# V1_0.net
KiCad netlist of a schematic drawn in Altium Designer
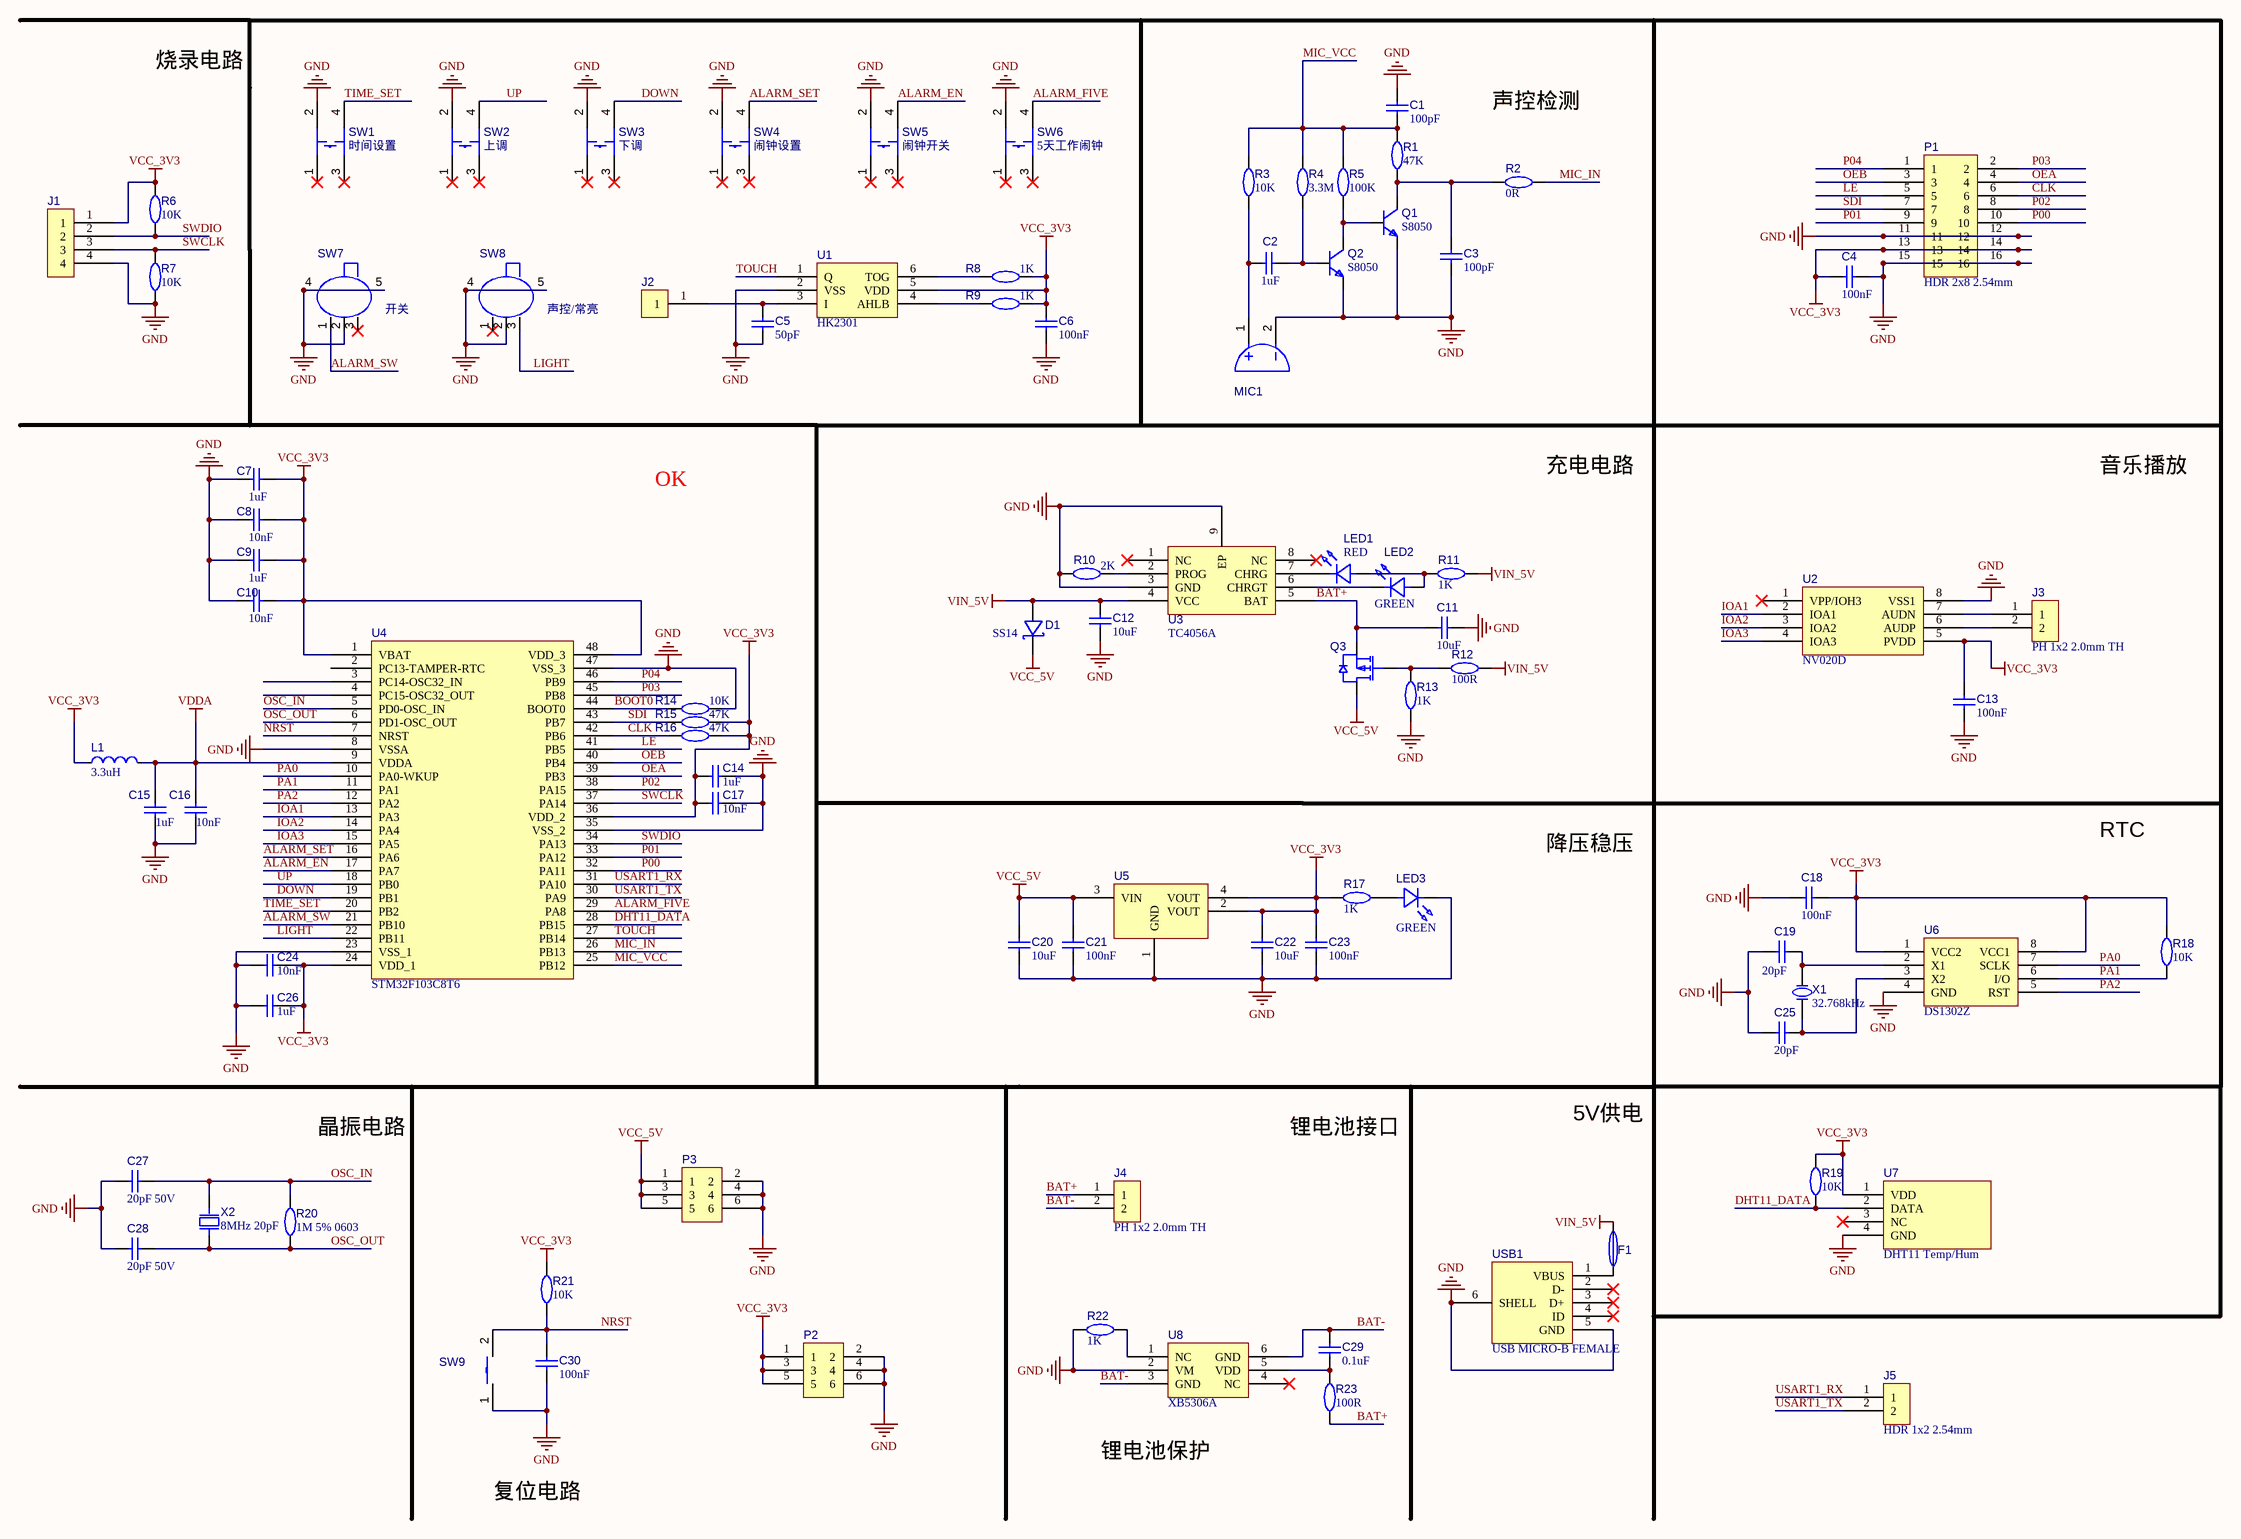
[diagram p0: 温湿度闹钟_V1.0.SchDoc]

(export (version "E")
  (design (tool "Eeschema 10.0.6"))
  (components
    (comp (ref "C1")
      (value "100pF")
      (footprint "C0603")
      (description "贴片电容")
      (libsource (lib "ADlib") (part "CAP_C0603_50V_10nF 50V"))
    )
    (comp (ref "C2")
      (value "1uF")
      (footprint "C0603")
      (description "贴片电容")
      (libsource (lib "ADlib") (part "CAP_C0603_50V_10nF 50V"))
    )
    (comp (ref "C3")
      (value "100pF")
      (footprint "C0603")
      (description "贴片电容")
      (libsource (lib "ADlib") (part "CAP_C0603_50V_10nF 50V"))
    )
    (comp (ref "C4")
      (value "100nF")
      (footprint "C0603")
      (description "贴片电容")
      (libsource (lib "ADlib") (part "CAP_C0603_50V_10nF 50V"))
    )
    (comp (ref "C5")
      (value "50pF")
      (footprint "C0603")
      (description "贴片电容")
      (libsource (lib "ADlib") (part "CAP_C0603_50V_10nF 50V"))
    )
    (comp (ref "C6")
      (value "100nF")
      (footprint "C0603")
      (description "贴片电容")
      (libsource (lib "ADlib") (part "CAP_C0603_50V_10nF 50V"))
    )
    (comp (ref "C7")
      (value "1uF")
      (footprint "C0603")
      (description "贴片电容")
      (libsource (lib "ADlib") (part "CAP_C0603_50V_10nF 50V"))
    )
    (comp (ref "C8")
      (value "10nF")
      (footprint "C0603")
      (description "贴片电容")
      (libsource (lib "ADlib") (part "CAP_C0603_50V_10nF 50V"))
    )
    (comp (ref "C9")
      (value "1uF")
      (footprint "C0603")
      (description "贴片电容")
      (libsource (lib "ADlib") (part "CAP_C0603_50V_10nF 50V"))
    )
    (comp (ref "C10")
      (value "10nF")
      (footprint "C0603")
      (description "贴片电容")
      (libsource (lib "ADlib") (part "CAP_C0603_50V_10nF 50V"))
    )
    (comp (ref "C11")
      (value "10uF")
      (footprint "C0603")
      (description "贴片电容")
      (libsource (lib "ADlib") (part "CAP_C0603_50V_10nF 50V"))
    )
    (comp (ref "C12")
      (value "10uF")
      (footprint "C0603")
      (description "贴片电容")
      (libsource (lib "ADlib") (part "CAP_C0603_50V_10nF 50V"))
    )
    (comp (ref "C13")
      (value "100nF")
      (footprint "C0603")
      (description "贴片电容")
      (libsource (lib "ADlib") (part "CAP_C0603_50V_10nF 50V"))
    )
    (comp (ref "C14")
      (value "1uF")
      (footprint "C0603")
      (description "贴片电容")
      (libsource (lib "ADlib") (part "CAP_C0603_50V_10nF 50V"))
    )
    (comp (ref "C15")
      (value "1uF")
      (footprint "C0603")
      (description "贴片电容")
      (libsource (lib "ADlib") (part "CAP_C0603_50V_10nF 50V"))
    )
    (comp (ref "C16")
      (value "10nF")
      (footprint "C0603")
      (description "贴片电容")
      (libsource (lib "ADlib") (part "CAP_C0603_50V_10nF 50V"))
    )
    (comp (ref "C17")
      (value "10nF")
      (footprint "C0603")
      (description "贴片电容")
      (libsource (lib "ADlib") (part "CAP_C0603_50V_10nF 50V"))
    )
    (comp (ref "C18")
      (value "100nF")
      (footprint "C0603")
      (description "贴片电容")
      (libsource (lib "ADlib") (part "CAP_C0603_50V_10nF 50V"))
    )
    (comp (ref "C19")
      (value "20pF")
      (footprint "C0603")
      (description "贴片电容")
      (libsource (lib "ADlib") (part "CAP_C0603_50V"))
    )
    (comp (ref "C20")
      (value "10uF")
      (footprint "C0603")
      (description "贴片电容")
      (libsource (lib "ADlib") (part "CAP_C0603_50V_10nF 50V"))
    )
    (comp (ref "C21")
      (value "100nF")
      (footprint "C0603")
      (description "贴片电容")
      (libsource (lib "ADlib") (part "CAP_C0603_50V_10nF 50V"))
    )
    (comp (ref "C22")
      (value "10uF")
      (footprint "C0603")
      (description "贴片电容")
      (libsource (lib "ADlib") (part "CAP_C0603_50V_10nF 50V"))
    )
    (comp (ref "C23")
      (value "100nF")
      (footprint "C0603")
      (description "贴片电容")
      (libsource (lib "ADlib") (part "CAP_C0603_50V_10nF 50V"))
    )
    (comp (ref "C24")
      (value "10nF")
      (footprint "C0603")
      (description "贴片电容")
      (libsource (lib "ADlib") (part "CAP_C0603_50V_10nF 50V"))
    )
    (comp (ref "C25")
      (value "20pF")
      (footprint "C0603")
      (description "贴片电容")
      (libsource (lib "ADlib") (part "CAP_C0603_50V"))
    )
    (comp (ref "C26")
      (value "1uF")
      (footprint "C0603")
      (description "贴片电容")
      (libsource (lib "ADlib") (part "CAP_C0603_50V_10nF 50V"))
    )
    (comp (ref "C27")
      (value "20pF 50V")
      (footprint "C0603")
      (description "贴片电容")
      (libsource (lib "ADlib") (part "CAP_C0603_50V"))
    )
    (comp (ref "C28")
      (value "20pF 50V")
      (footprint "C0603")
      (description "贴片电容")
      (libsource (lib "ADlib") (part "CAP_C0603_50V"))
    )
    (comp (ref "C29")
      (value "0.1uF")
      (footprint "C0603")
      (description "贴片电容")
      (libsource (lib "ADlib") (part "CAP_C0603_50V_10nF 50V"))
    )
    (comp (ref "C30")
      (value "100nF")
      (footprint "C0603")
      (description "贴片电容")
      (libsource (lib "ADlib") (part "CAP_C0603_50V_10nF 50V"))
    )
    (comp (ref "D1")
      (value "SS14")
      (footprint "SMA_L4.3-W2.6-LS5.2-RD")
      (description "肖特基二极管")
      (libsource (lib "ADlib") (part "SS14"))
    )
    (comp (ref "F1")
      (value "PPTC 500mA 13.2V")
      (footprint "F1210")
      (description "保险丝")
      (libsource (lib "ADlib") (part "FUSE_PPTC_500MA_TBD"))
    )
    (comp (ref "J1")
      (value "HDR 1x4 2.54mm")
      (footprint "HDR-TH_4P-P2.54-V-M")
      (description "直插排针")
      (libsource (lib "ADlib") (part "HDR_1x04_2.54mm_TH"))
    )
    (comp (ref "J2")
      (value "HDR 1x1 2.54mm")
      (footprint "HDR-TH_1P-P2.54-V-M")
      (description "直插排针")
      (libsource (lib "ADlib") (part "HDR_1x01_2.54mm_TH"))
    )
    (comp (ref "J3")
      (value "PH 1x2 2.0mm TH")
      (footprint "CONN-TH_2P-P2.00_HC-PH-2A-M")
      (description "直插线对板针座")
      (libsource (lib "ADlib") (part "HDR_PH_1x02_2.0mm_TH"))
    )
    (comp (ref "J4")
      (value "PH 1x2 2.0mm TH")
      (footprint "CONN-TH_2P-P2.00_HC-PH-2A-M")
      (description "直插线对板针座")
      (libsource (lib "ADlib") (part "HDR_PH_1x02_2.0mm_TH"))
    )
    (comp (ref "J5")
      (value "HDR 1x2 2.54mm")
      (footprint "HDR-TH_2P-P2.54-V-M")
      (description "直插排针")
      (libsource (lib "ADlib") (part "HDR_1x02_2.54mm_TH"))
    )
    (comp (ref "L1")
      (value "3.3uH")
      (footprint "L0603")
      (description "贴片电感")
      (libsource (lib "ADlib") (part "L_0603_15MA_3.3uH"))
    )
    (comp (ref "LED1")
      (value "RED")
      (footprint "LED0603")
      (description "发光二极管")
      (libsource (lib "ADlib") (part "LED_RED_20MA_TBD"))
    )
    (comp (ref "LED2")
      (value "GREEN")
      (footprint "LED0603")
      (description "发光二极管")
      (libsource (lib "ADlib") (part "LED_RED_20MA_TBD"))
    )
    (comp (ref "LED3")
      (value "GREEN")
      (footprint "LED0603")
      (description "发光二极管")
      (libsource (lib "ADlib") (part "LED_RED_20MA_TBD"))
    )
    (comp (ref "MIC1")
      (value "GMI6050P-60DB")
      (footprint "MIC-TH_BD6.0-P1.90-D0.4-L-RD")
      (description "咪头")
      (libsource (lib "ADlib") (part "GMI6050P-60DB"))
    )
    (comp (ref "P1")
      (value "HDR 2x8 2.54mm")
      (footprint "HDR-TH_16P-P2.54-V-M-R2-C8-S2.54")
      (description "排针")
      (libsource (lib "ADlib") (part "HDR_2x08_2.54mm_TH"))
    )
    (comp (ref "P2")
      (value "HDR 2x3 2.54mm")
      (footprint "HDR-TH_6P-P2.54-V-M-R2-C3-S2.54")
      (description "双排排针")
      (libsource (lib "ADlib") (part "HDR_2x03_2.54mm_TH"))
    )
    (comp (ref "P3")
      (value "HDR 2x3 2.54mm")
      (footprint "HDR-TH_6P-P2.54-V-M-R2-C3-S2.54")
      (description "双排排针")
      (libsource (lib "ADlib") (part "HDR_2x03_2.54mm_TH"))
    )
    (comp (ref "Q1")
      (value "S8050")
      (footprint "SOT-23-3_L2.9-W1.3-P1.90-LS2.3-BR")
      (description "三极管NPN")
      (libsource (lib "ADlib") (part "S8050"))
    )
    (comp (ref "Q2")
      (value "S8050")
      (footprint "SOT-23-3_L2.9-W1.3-P1.90-LS2.3-BR")
      (description "三极管NPN")
      (libsource (lib "ADlib") (part "S8050"))
    )
    (comp (ref "Q3")
      (value "P-MOSFET 30V 4A")
      (footprint "SOT-23_L2.9-W1.3-P1.90-LS2.4-BR")
      (description "P沟道场效应管")
      (libsource (lib "ADlib") (part "AO3401A"))
    )
    (comp (ref "R1")
      (value "47K")
      (footprint "R0603")
      (description "贴片电阻")
      (libsource (lib "ADlib") (part "R_0603_100MW"))
    )
    (comp (ref "R2")
      (value "0R")
      (footprint "R0603")
      (description "贴片电阻")
      (libsource (lib "ADlib") (part "R_0603_100MW"))
    )
    (comp (ref "R3")
      (value "10K")
      (footprint "R0603")
      (description "贴片电阻")
      (libsource (lib "ADlib") (part "R_0603_100MW"))
    )
    (comp (ref "R4")
      (value "3.3M")
      (footprint "R0603")
      (description "贴片电阻")
      (libsource (lib "ADlib") (part "R_0603_100MW"))
    )
    (comp (ref "R5")
      (value "100K")
      (footprint "R0603")
      (description "贴片电阻")
      (libsource (lib "ADlib") (part "R_0603_100MW"))
    )
    (comp (ref "R6")
      (value "10K")
      (footprint "R0603")
      (description "贴片电阻")
      (libsource (lib "ADlib") (part "R_0603_100MW"))
    )
    (comp (ref "R7")
      (value "10K")
      (footprint "R0603")
      (description "贴片电阻")
      (libsource (lib "ADlib") (part "R_0603_100MW"))
    )
    (comp (ref "R8")
      (value "1K")
      (footprint "R0603")
      (description "贴片电阻")
      (libsource (lib "ADlib") (part "R_0603_100MW"))
    )
    (comp (ref "R9")
      (value "1K")
      (footprint "R0603")
      (description "贴片电阻")
      (libsource (lib "ADlib") (part "R_0603_100MW"))
    )
    (comp (ref "R10")
      (value "2K")
      (footprint "R0603")
      (description "贴片电阻")
      (libsource (lib "ADlib") (part "R_0603_100MW"))
    )
    (comp (ref "R11")
      (value "1K")
      (footprint "R0603")
      (description "贴片电阻")
      (libsource (lib "ADlib") (part "R_0603_100MW"))
    )
    (comp (ref "R12")
      (value "100R")
      (footprint "R0603")
      (description "贴片电阻")
      (libsource (lib "ADlib") (part "R_0603_100MW"))
    )
    (comp (ref "R13")
      (value "1K")
      (footprint "R0603")
      (description "贴片电阻")
      (libsource (lib "ADlib") (part "R_0603_100MW"))
    )
    (comp (ref "R14")
      (value "10K")
      (footprint "R0603")
      (description "贴片电阻")
      (libsource (lib "ADlib") (part "R_0603_100MW"))
    )
    (comp (ref "R15")
      (value "47K")
      (footprint "R0603")
      (description "贴片电阻")
      (libsource (lib "ADlib") (part "R_0603_100MW"))
    )
    (comp (ref "R16")
      (value "47K")
      (footprint "R0603")
      (description "贴片电阻")
      (libsource (lib "ADlib") (part "R_0603_100MW"))
    )
    (comp (ref "R17")
      (value "1K")
      (footprint "R0603")
      (description "贴片电阻")
      (libsource (lib "ADlib") (part "R_0603_100MW"))
    )
    (comp (ref "R18")
      (value "10K")
      (footprint "R0603")
      (description "贴片电阻")
      (libsource (lib "ADlib") (part "R_0603_100MW"))
    )
    (comp (ref "R19")
      (value "10K")
      (footprint "R0603")
      (description "贴片电阻")
      (libsource (lib "ADlib") (part "R_0603_100MW"))
    )
    (comp (ref "R20")
      (value "1M 5% 0603")
      (footprint "R0603")
      (description "贴片电阻")
      (libsource (lib "ADlib") (part "R_0603_100MW"))
    )
    (comp (ref "R21")
      (value "10K")
      (footprint "R0603")
      (description "贴片电阻")
      (libsource (lib "ADlib") (part "R_0603_100MW"))
    )
    (comp (ref "R22")
      (value "1K")
      (footprint "R0603")
      (description "贴片电阻")
      (libsource (lib "ADlib") (part "R_0603_100MW"))
    )
    (comp (ref "R23")
      (value "100R")
      (footprint "R0603")
      (description "贴片电阻")
      (libsource (lib "ADlib") (part "R_0603_100MW"))
    )
    (comp (ref "SW1")
      (value "时间设置")
      (footprint "SW-TH_4P-L6.0-W6.0-P4.50-LS6.5")
      (description "直插轻触开关")
      (libsource (lib "ADlib") (part "SW_TACT_6x6_7H_TH"))
    )
    (comp (ref "SW2")
      (value "上调")
      (footprint "SW-TH_4P-L6.0-W6.0-P4.50-LS6.5")
      (description "直插轻触开关")
      (libsource (lib "ADlib") (part "SW_TACT_6x6_7H_TH"))
    )
    (comp (ref "SW3")
      (value "下调")
      (footprint "SW-TH_4P-L6.0-W6.0-P4.50-LS6.5")
      (description "直插轻触开关")
      (libsource (lib "ADlib") (part "SW_TACT_6x6_7H_TH"))
    )
    (comp (ref "SW4")
      (value "闹钟设置")
      (footprint "SW-TH_4P-L6.0-W6.0-P4.50-LS6.5")
      (description "直插轻触开关")
      (libsource (lib "ADlib") (part "SW_TACT_6x6_7H_TH"))
    )
    (comp (ref "SW5")
      (value "闹钟开关")
      (footprint "SW-TH_4P-L6.0-W6.0-P4.50-LS6.5")
      (description "直插轻触开关")
      (libsource (lib "ADlib") (part "SW_TACT_6x6_7H_TH"))
    )
    (comp (ref "SW6")
      (value "5天工作闹钟")
      (footprint "SW-TH_4P-L6.0-W6.0-P4.50-LS6.5")
      (description "直插轻触开关")
      (libsource (lib "ADlib") (part "SW_TACT_6x6_7H_TH"))
    )
    (comp (ref "SW7")
      (value "SW_SS12D07VG4")
      (footprint "SW-TH_SS12D07VG4")
      (description "滑动开关")
      (libsource (lib "ADlib") (part "SW_SS12D07VG4"))
    )
    (comp (ref "SW8")
      (value "SW_SS12D07VG4")
      (footprint "SW-TH_SS12D07VG4")
      (description "滑动开关")
      (libsource (lib "ADlib") (part "SW_SS12D07VG4"))
    )
    (comp (ref "SW9")
      (value "TACT 6.0x3.6mm")
      (footprint "SW-SMD_L6.0-W3.3-LS8.0")
      (description "轻触开关")
      (libsource (lib "ADlib") (part "SW_TACT_6036_25H_SMD"))
    )
    (comp (ref "U1")
      (value "HK2301")
      (footprint "SOT-23-6_L2.9-W1.6-P0.95-LS2.8-BL")
      (description "触摸芯片")
      (libsource (lib "ADlib") (part "HK2301"))
    )
    (comp (ref "U2")
      (value "NV020D")
      (footprint "SOP-8_L4.9-W3.9-P1.27-LS6.0-BL-1")
      (description "音频接口芯片")
      (libsource (lib "ADlib") (part "NV020D"))
    )
    (comp (ref "U3")
      (value "TC4056A")
      (footprint "ESOP-8_L4.9-W3.9-P1.27-LS6.0-BL-EP")
      (description "锂电池充电芯片")
      (libsource (lib "ADlib") (part "TC4056A"))
    )
    (comp (ref "U4")
      (value "STM32F103C8T6")
      (footprint "LQFP-48_L7.0-W7.0-P0.50-LS9.0-BL")
      (libsource (lib "ADlib") (part "STM32F103C8T6"))
    )
    (comp (ref "U5")
      (value "LDO 3.3V 1A")
      (footprint "SOT-223-3_L6.5-W3.4-P2.30-LS7.0-BR")
      (description "线性稳压器")
      (libsource (lib "ADlib") (part "AMS1117-3.3"))
    )
    (comp (ref "U6")
      (value "DS1302Z")
      (footprint "SOP-8_L4.9-W3.9-P1.27-LS6.0-BL-1")
      (description "实时时钟芯片")
      (libsource (lib "ADlib") (part "DS1302Z"))
    )
    (comp (ref "U7")
      (value "DHT11 Temp/Hum")
      (footprint "SENSOR-TH_DHT11")
      (description "温湿度传感器")
      (libsource (lib "ADlib") (part "DHT11"))
    )
    (comp (ref "U8")
      (value "XB5306A")
      (footprint "SOT-23-6_L2.9-W1.6-P0.95-LS2.8-BR")
      (description "锂电池保护芯片")
      (libsource (lib "ADlib") (part "XB5306A"))
    )
    (comp (ref "USB1")
      (value "USB MICRO-B FEMALE")
      (footprint "MICRO-USB-SMD_MICRO-XNJ-ZB")
      (description "Micro-B")
      (libsource (lib "ADlib") (part "CONN_USB_MICRO-B_SMT"))
    )
    (comp (ref "X1")
      (value "32.768kHz")
      (footprint "OSC-TH_BD3.1-P0.8-D0.3")
      (description "32.768kHz 直插晶振")
      (libsource (lib "ADlib") (part "XTAL_32.768K_TH"))
    )
    (comp (ref "X2")
      (value "8MHz 20pF")
      (footprint "ADlib:OSC-TH_L10.0-W4.5-P5.00")
      (description "直插晶振")
      (libsource (lib "ADlib") (part "XTAL_8M_20PF_TH"))
    )
  )
  (nets
    (net (code "1") (name "/ALARM_EN") (class "Default")
      (node (ref "SW5") (pin "4") (pinfunction "4_4") (pintype "passive"))
      (node (ref "U4") (pin "17") (pinfunction "PA7_17") (pintype "passive"))
    )
    (net (code "2") (name "/ALARM_FIVE") (class "Default")
      (node (ref "SW6") (pin "4") (pinfunction "4_4") (pintype "passive"))
      (node (ref "U4") (pin "29") (pinfunction "PA8_29") (pintype "passive"))
    )
    (net (code "3") (name "/ALARM_SET") (class "Default")
      (node (ref "SW4") (pin "4") (pinfunction "4_4") (pintype "passive"))
      (node (ref "U4") (pin "16") (pinfunction "PA6_16") (pintype "passive"))
    )
    (net (code "4") (name "/ALARM_SW") (class "Default")
      (node (ref "SW7") (pin "1") (pinfunction "1_1") (pintype "passive"))
      (node (ref "U4") (pin "21") (pinfunction "PB10_21") (pintype "passive"))
    )
    (net (code "5") (name "/BAT+") (class "Default")
      (node (ref "C11") (pin "2") (pinfunction "2_2") (pintype "passive"))
      (node (ref "J4") (pin "1") (pinfunction "1_1") (pintype "passive"))
      (node (ref "Q3") (pin "2") (pinfunction "S_2") (pintype "passive"))
      (node (ref "R23") (pin "1") (pinfunction "1_1") (pintype "passive"))
      (node (ref "U3") (pin "5") (pinfunction "BAT_5") (pintype "passive"))
    )
    (net (code "6") (name "/BAT-") (class "Default")
      (node (ref "C29") (pin "2") (pinfunction "2_2") (pintype "passive"))
      (node (ref "J4") (pin "2") (pinfunction "2_2") (pintype "passive"))
      (node (ref "U8") (pin "3") (pinfunction "GND_3") (pintype "passive"))
      (node (ref "U8") (pin "6") (pinfunction "GND_6") (pintype "passive"))
    )
    (net (code "7") (name "/BOOT0") (class "Default")
      (node (ref "R14") (pin "2") (pinfunction "2_2") (pintype "passive"))
      (node (ref "U4") (pin "44") (pinfunction "BOOT0_44") (pintype "passive"))
    )
    (net (code "8") (name "/CLK") (class "Default")
      (node (ref "P1") (pin "6") (pinfunction "6_6") (pintype "passive"))
      (node (ref "R16") (pin "1") (pinfunction "1_1") (pintype "passive"))
      (node (ref "U4") (pin "42") (pinfunction "PB6_42") (pintype "passive"))
    )
    (net (code "9") (name "/DHT11_DATA") (class "Default")
      (node (ref "R19") (pin "1") (pinfunction "1_1") (pintype "passive"))
      (node (ref "U4") (pin "28") (pinfunction "PB15_28") (pintype "passive"))
      (node (ref "U7") (pin "2") (pinfunction "DATA_2") (pintype "passive"))
    )
    (net (code "10") (name "/DOWN") (class "Default")
      (node (ref "SW3") (pin "4") (pinfunction "4_4") (pintype "passive"))
      (node (ref "U4") (pin "19") (pinfunction "PB1_19") (pintype "passive"))
    )
    (net (code "11") (name "/IOA1") (class "Default")
      (node (ref "U2") (pin "2") (pinfunction "IOA1_2") (pintype "passive"))
      (node (ref "U4") (pin "13") (pinfunction "PA3_13") (pintype "passive"))
    )
    (net (code "12") (name "/IOA2") (class "Default")
      (node (ref "U2") (pin "3") (pinfunction "IOA2_3") (pintype "passive"))
      (node (ref "U4") (pin "14") (pinfunction "PA4_14") (pintype "passive"))
    )
    (net (code "13") (name "/IOA3") (class "Default")
      (node (ref "U2") (pin "4") (pinfunction "IOA3_4") (pintype "passive"))
      (node (ref "U4") (pin "15") (pinfunction "PA5_15") (pintype "passive"))
    )
    (net (code "14") (name "/LE") (class "Default")
      (node (ref "P1") (pin "5") (pinfunction "5_5") (pintype "passive"))
      (node (ref "U4") (pin "41") (pinfunction "PB5_41") (pintype "passive"))
    )
    (net (code "15") (name "/LIGHT") (class "Default")
      (node (ref "SW8") (pin "3") (pinfunction "3_3") (pintype "passive"))
      (node (ref "U4") (pin "22") (pinfunction "PB11_22") (pintype "passive"))
    )
    (net (code "16") (name "/MIC_IN") (class "Default")
      (node (ref "R2") (pin "1") (pinfunction "1_1") (pintype "passive"))
      (node (ref "U4") (pin "26") (pinfunction "PB13_26") (pintype "passive"))
    )
    (net (code "17") (name "/MIC_VCC") (class "Default")
      (node (ref "C1") (pin "2") (pinfunction "2_2") (pintype "passive"))
      (node (ref "R1") (pin "2") (pinfunction "2_2") (pintype "passive"))
      (node (ref "R3") (pin "2") (pinfunction "2_2") (pintype "passive"))
      (node (ref "R4") (pin "2") (pinfunction "2_2") (pintype "passive"))
      (node (ref "R5") (pin "2") (pinfunction "2_2") (pintype "passive"))
      (node (ref "U4") (pin "25") (pinfunction "PB12_25") (pintype "passive"))
    )
    (net (code "18") (name "/NRST") (class "Default")
      (node (ref "C30") (pin "1") (pinfunction "1_1") (pintype "passive"))
      (node (ref "R21") (pin "1") (pinfunction "1_1") (pintype "passive"))
      (node (ref "SW9") (pin "2") (pinfunction "2_2") (pintype "passive"))
      (node (ref "U4") (pin "7") (pinfunction "NRST_7") (pintype "passive"))
    )
    (net (code "19") (name "/OEA") (class "Default")
      (node (ref "P1") (pin "4") (pinfunction "4_4") (pintype "passive"))
      (node (ref "U4") (pin "39") (pinfunction "PB3_39") (pintype "passive"))
    )
    (net (code "20") (name "/OEB") (class "Default")
      (node (ref "P1") (pin "3") (pinfunction "3_3") (pintype "passive"))
      (node (ref "U4") (pin "40") (pinfunction "PB4_40") (pintype "passive"))
    )
    (net (code "21") (name "/OSC_IN") (class "Default")
      (node (ref "C27") (pin "2") (pinfunction "2_2") (pintype "passive"))
      (node (ref "R20") (pin "2") (pinfunction "2_2") (pintype "passive"))
      (node (ref "U4") (pin "5") (pinfunction "PD0-OSC_IN_5") (pintype "passive"))
      (node (ref "X2") (pin "1") (pinfunction "OSC1_1") (pintype "passive"))
    )
    (net (code "22") (name "/OSC_OUT") (class "Default")
      (node (ref "C28") (pin "2") (pinfunction "2_2") (pintype "passive"))
      (node (ref "R20") (pin "1") (pinfunction "1_1") (pintype "passive"))
      (node (ref "U4") (pin "6") (pinfunction "PD1-OSC_OUT_6") (pintype "passive"))
      (node (ref "X2") (pin "2") (pinfunction "OSC2_2") (pintype "passive"))
    )
    (net (code "23") (name "/P00") (class "Default")
      (node (ref "P1") (pin "10") (pinfunction "10_10") (pintype "passive"))
      (node (ref "U4") (pin "32") (pinfunction "PA11_32") (pintype "passive"))
    )
    (net (code "24") (name "/P01") (class "Default")
      (node (ref "P1") (pin "9") (pinfunction "9_9") (pintype "passive"))
      (node (ref "U4") (pin "33") (pinfunction "PA12_33") (pintype "passive"))
    )
    (net (code "25") (name "/P02") (class "Default")
      (node (ref "P1") (pin "8") (pinfunction "8_8") (pintype "passive"))
      (node (ref "U4") (pin "38") (pinfunction "PA15_38") (pintype "passive"))
    )
    (net (code "26") (name "/P03") (class "Default")
      (node (ref "P1") (pin "2") (pinfunction "2_2") (pintype "passive"))
      (node (ref "U4") (pin "45") (pinfunction "PB8_45") (pintype "passive"))
    )
    (net (code "27") (name "/P04") (class "Default")
      (node (ref "P1") (pin "1") (pinfunction "1_1") (pintype "passive"))
      (node (ref "U4") (pin "46") (pinfunction "PB9_46") (pintype "passive"))
    )
    (net (code "28") (name "/PA0") (class "Default")
      (node (ref "U4") (pin "10") (pinfunction "PA0-WKUP_10") (pintype "passive"))
      (node (ref "U6") (pin "7") (pinfunction "SCLK_7") (pintype "passive"))
    )
    (net (code "29") (name "/PA1") (class "Default")
      (node (ref "R18") (pin "1") (pinfunction "1_1") (pintype "passive"))
      (node (ref "U4") (pin "11") (pinfunction "PA1_11") (pintype "passive"))
      (node (ref "U6") (pin "6") (pinfunction "I/O_6") (pintype "passive"))
    )
    (net (code "30") (name "/PA2") (class "Default")
      (node (ref "U4") (pin "12") (pinfunction "PA2_12") (pintype "passive"))
      (node (ref "U6") (pin "5") (pinfunction "RST_5") (pintype "passive"))
    )
    (net (code "31") (name "/SDI") (class "Default")
      (node (ref "P1") (pin "7") (pinfunction "7_7") (pintype "passive"))
      (node (ref "R15") (pin "1") (pinfunction "1_1") (pintype "passive"))
      (node (ref "U4") (pin "43") (pinfunction "PB7_43") (pintype "passive"))
    )
    (net (code "32") (name "/SWCLK") (class "Default")
      (node (ref "J1") (pin "3") (pinfunction "3_3") (pintype "passive"))
      (node (ref "R7") (pin "2") (pinfunction "2_2") (pintype "passive"))
      (node (ref "U4") (pin "37") (pinfunction "PA14_37") (pintype "passive"))
    )
    (net (code "33") (name "/SWDIO") (class "Default")
      (node (ref "J1") (pin "2") (pinfunction "2_2") (pintype "passive"))
      (node (ref "R6") (pin "1") (pinfunction "1_1") (pintype "passive"))
      (node (ref "U4") (pin "34") (pinfunction "PA13_34") (pintype "passive"))
    )
    (net (code "34") (name "/TIME_SET") (class "Default")
      (node (ref "SW1") (pin "4") (pinfunction "4_4") (pintype "passive"))
      (node (ref "U4") (pin "20") (pinfunction "PB2_20") (pintype "passive"))
    )
    (net (code "35") (name "/TOUCH") (class "Default")
      (node (ref "U1") (pin "1") (pinfunction "Q_1") (pintype "passive"))
      (node (ref "U4") (pin "27") (pinfunction "PB14_27") (pintype "passive"))
    )
    (net (code "36") (name "/UP") (class "Default")
      (node (ref "SW2") (pin "4") (pinfunction "4_4") (pintype "passive"))
      (node (ref "U4") (pin "18") (pinfunction "PB0_18") (pintype "passive"))
    )
    (net (code "37") (name "/USART1_RX") (class "Default")
      (node (ref "J5") (pin "1") (pinfunction "1_1") (pintype "passive"))
      (node (ref "U4") (pin "31") (pinfunction "PA10_31") (pintype "passive"))
    )
    (net (code "38") (name "/USART1_TX") (class "Default")
      (node (ref "J5") (pin "2") (pinfunction "2_2") (pintype "passive"))
      (node (ref "U4") (pin "30") (pinfunction "PA9_30") (pintype "passive"))
    )
    (net (code "39") (name "GND") (class "Default")
      (node (ref "C1") (pin "1") (pinfunction "1_1") (pintype "passive"))
      (node (ref "C10") (pin "1") (pinfunction "1_1") (pintype "passive"))
      (node (ref "C11") (pin "1") (pinfunction "1_1") (pintype "passive"))
      (node (ref "C12") (pin "1") (pinfunction "1_1") (pintype "passive"))
      (node (ref "C13") (pin "2") (pinfunction "2_2") (pintype "passive"))
      (node (ref "C14") (pin "2") (pinfunction "2_2") (pintype "passive"))
      (node (ref "C15") (pin "1") (pinfunction "1_1") (pintype "passive"))
      (node (ref "C16") (pin "1") (pinfunction "1_1") (pintype "passive"))
      (node (ref "C17") (pin "1") (pinfunction "1_1") (pintype "passive"))
      (node (ref "C18") (pin "1") (pinfunction "1_1") (pintype "passive"))
      (node (ref "C19") (pin "1") (pinfunction "1_1") (pintype "passive"))
      (node (ref "C20") (pin "2") (pinfunction "2_2") (pintype "passive"))
      (node (ref "C21") (pin "2") (pinfunction "2_2") (pintype "passive"))
      (node (ref "C22") (pin "2") (pinfunction "2_2") (pintype "passive"))
      (node (ref "C23") (pin "2") (pinfunction "2_2") (pintype "passive"))
      (node (ref "C24") (pin "2") (pinfunction "2_2") (pintype "passive"))
      (node (ref "C25") (pin "1") (pinfunction "1_1") (pintype "passive"))
      (node (ref "C26") (pin "2") (pinfunction "2_2") (pintype "passive"))
      (node (ref "C27") (pin "1") (pinfunction "1_1") (pintype "passive"))
      (node (ref "C28") (pin "1") (pinfunction "1_1") (pintype "passive"))
      (node (ref "C3") (pin "2") (pinfunction "2_2") (pintype "passive"))
      (node (ref "C30") (pin "2") (pinfunction "2_2") (pintype "passive"))
      (node (ref "C4") (pin "2") (pinfunction "2_2") (pintype "passive"))
      (node (ref "C5") (pin "1") (pinfunction "1_1") (pintype "passive"))
      (node (ref "C6") (pin "1") (pinfunction "1_1") (pintype "passive"))
      (node (ref "C7") (pin "1") (pinfunction "1_1") (pintype "passive"))
      (node (ref "C8") (pin "1") (pinfunction "1_1") (pintype "passive"))
      (node (ref "C9") (pin "1") (pinfunction "1_1") (pintype "passive"))
      (node (ref "J1") (pin "4") (pinfunction "4_4") (pintype "passive"))
      (node (ref "LED3") (pin "1") (pinfunction "K_1") (pintype "passive"))
      (node (ref "MIC1") (pin "2") (pinfunction "2_2") (pintype "passive"))
      (node (ref "P1") (pin "11") (pinfunction "11_11") (pintype "passive"))
      (node (ref "P1") (pin "12") (pinfunction "12_12") (pintype "passive"))
      (node (ref "P1") (pin "15") (pinfunction "15_15") (pintype "passive"))
      (node (ref "P1") (pin "16") (pinfunction "16_16") (pintype "passive"))
      (node (ref "P2") (pin "2") (pinfunction "2_2") (pintype "passive"))
      (node (ref "P2") (pin "4") (pinfunction "4_4") (pintype "passive"))
      (node (ref "P2") (pin "6") (pinfunction "6_6") (pintype "passive"))
      (node (ref "P3") (pin "2") (pinfunction "2_2") (pintype "passive"))
      (node (ref "P3") (pin "4") (pinfunction "4_4") (pintype "passive"))
      (node (ref "P3") (pin "6") (pinfunction "6_6") (pintype "passive"))
      (node (ref "Q1") (pin "2") (pinfunction "E_2") (pintype "passive"))
      (node (ref "Q2") (pin "2") (pinfunction "E_2") (pintype "passive"))
      (node (ref "R10") (pin "1") (pinfunction "1_1") (pintype "passive"))
      (node (ref "R13") (pin "1") (pinfunction "1_1") (pintype "passive"))
      (node (ref "R14") (pin "1") (pinfunction "1_1") (pintype "passive"))
      (node (ref "R22") (pin "1") (pinfunction "1_1") (pintype "passive"))
      (node (ref "R7") (pin "1") (pinfunction "1_1") (pintype "passive"))
      (node (ref "SW1") (pin "2") (pinfunction "2_2") (pintype "passive"))
      (node (ref "SW2") (pin "2") (pinfunction "2_2") (pintype "passive"))
      (node (ref "SW3") (pin "2") (pinfunction "2_2") (pintype "passive"))
      (node (ref "SW4") (pin "2") (pinfunction "2_2") (pintype "passive"))
      (node (ref "SW5") (pin "2") (pinfunction "2_2") (pintype "passive"))
      (node (ref "SW6") (pin "2") (pinfunction "2_2") (pintype "passive"))
      (node (ref "SW7") (pin "2") (pinfunction "2_2") (pintype "passive"))
      (node (ref "SW7") (pin "4") (pinfunction "4_4") (pintype "passive"))
      (node (ref "SW7") (pin "5") (pinfunction "5_5") (pintype "passive"))
      (node (ref "SW8") (pin "2") (pinfunction "2_2") (pintype "passive"))
      (node (ref "SW8") (pin "4") (pinfunction "4_4") (pintype "passive"))
      (node (ref "SW8") (pin "5") (pinfunction "5_5") (pintype "passive"))
      (node (ref "SW9") (pin "1") (pinfunction "1_1") (pintype "passive"))
      (node (ref "U1") (pin "2") (pinfunction "VSS_2") (pintype "passive"))
      (node (ref "U2") (pin "8") (pinfunction "VSS1_8") (pintype "passive"))
      (node (ref "U3") (pin "3") (pinfunction "GND_3") (pintype "passive"))
      (node (ref "U3") (pin "9") (pinfunction "EP_9") (pintype "passive"))
      (node (ref "U4") (pin "23") (pinfunction "VSS_1_23") (pintype "passive"))
      (node (ref "U4") (pin "35") (pinfunction "VSS_2_35") (pintype "passive"))
      (node (ref "U4") (pin "47") (pinfunction "VSS_3_47") (pintype "passive"))
      (node (ref "U4") (pin "8") (pinfunction "VSSA_8") (pintype "passive"))
      (node (ref "U5") (pin "1") (pinfunction "GND_1") (pintype "passive"))
      (node (ref "U6") (pin "4") (pinfunction "GND_4") (pintype "passive"))
      (node (ref "U7") (pin "4") (pinfunction "GND_4") (pintype "passive"))
      (node (ref "U8") (pin "2") (pinfunction "VM_2") (pintype "passive"))
      (node (ref "USB1") (pin "5") (pinfunction "GND_5") (pintype "passive"))
      (node (ref "USB1") (pin "6") (pinfunction "SHELL_6") (pintype "passive"))
    )
    (net (code "40") (name "Net-(C2-Pad2)") (class "Default")
      (node (ref "C2") (pin "2") (pinfunction "2_2") (pintype "passive"))
      (node (ref "MIC1") (pin "1") (pinfunction "1_1") (pintype "passive"))
      (node (ref "R3") (pin "1") (pinfunction "1_1") (pintype "passive"))
    )
    (net (code "41") (name "Net-(LED1-A)") (class "Default")
      (node (ref "LED1") (pin "2") (pinfunction "A_2") (pintype "passive"))
      (node (ref "LED2") (pin "2") (pinfunction "A_2") (pintype "passive"))
      (node (ref "R11") (pin "1") (pinfunction "1_1") (pintype "passive"))
    )
    (net (code "42") (name "Net-(LED1-K)") (class "Default")
      (node (ref "LED1") (pin "1") (pinfunction "K_1") (pintype "passive"))
      (node (ref "U3") (pin "7") (pinfunction "CHRG_7") (pintype "passive"))
    )
    (net (code "43") (name "Net-(LED2-K)") (class "Default")
      (node (ref "LED2") (pin "1") (pinfunction "K_1") (pintype "passive"))
      (node (ref "U3") (pin "6") (pinfunction "CHRGT_6") (pintype "passive"))
    )
    (net (code "44") (name "Net-(LED3-A)") (class "Default")
      (node (ref "LED3") (pin "2") (pinfunction "A_2") (pintype "passive"))
      (node (ref "R17") (pin "2") (pinfunction "2_2") (pintype "passive"))
    )
    (net (code "45") (name "Net-(Q1-B)") (class "Default")
      (node (ref "Q1") (pin "1") (pinfunction "B_1") (pintype "passive"))
      (node (ref "Q2") (pin "3") (pinfunction "C_3") (pintype "passive"))
      (node (ref "R5") (pin "1") (pinfunction "1_1") (pintype "passive"))
    )
    (net (code "46") (name "Net-(Q1-C)") (class "Default")
      (node (ref "C3") (pin "1") (pinfunction "1_1") (pintype "passive"))
      (node (ref "Q1") (pin "3") (pinfunction "C_3") (pintype "passive"))
      (node (ref "R1") (pin "1") (pinfunction "1_1") (pintype "passive"))
      (node (ref "R2") (pin "2") (pinfunction "2_2") (pintype "passive"))
    )
    (net (code "47") (name "Net-(Q2-B)") (class "Default")
      (node (ref "C2") (pin "1") (pinfunction "1_1") (pintype "passive"))
      (node (ref "Q2") (pin "1") (pinfunction "B_1") (pintype "passive"))
      (node (ref "R4") (pin "1") (pinfunction "1_1") (pintype "passive"))
    )
    (net (code "48") (name "Net-(Q3-G)") (class "Default")
      (node (ref "Q3") (pin "1") (pinfunction "G_1") (pintype "passive"))
      (node (ref "R12") (pin "1") (pinfunction "1_1") (pintype "passive"))
      (node (ref "R13") (pin "2") (pinfunction "2_2") (pintype "passive"))
    )
    (net (code "49") (name "Net-(R22-Pad2)") (class "Default")
      (node (ref "R22") (pin "2") (pinfunction "2_2") (pintype "passive"))
      (node (ref "U8") (pin "1") (pinfunction "NC_1") (pintype "passive"))
    )
    (net (code "50") (name "Net-(U1-AHLB)") (class "Default")
      (node (ref "R9") (pin "1") (pinfunction "1_1") (pintype "passive"))
      (node (ref "U1") (pin "4") (pinfunction "AHLB_4") (pintype "passive"))
    )
    (net (code "51") (name "Net-(U1-I)") (class "Default")
      (node (ref "C5") (pin "2") (pinfunction "2_2") (pintype "passive"))
      (node (ref "J2") (pin "1") (pinfunction "1_1") (pintype "passive"))
      (node (ref "U1") (pin "3") (pinfunction "I_3") (pintype "passive"))
    )
    (net (code "52") (name "Net-(U1-TOG)") (class "Default")
      (node (ref "R8") (pin "1") (pinfunction "1_1") (pintype "passive"))
      (node (ref "U1") (pin "6") (pinfunction "TOG_6") (pintype "passive"))
    )
    (net (code "53") (name "Net-(U2-AUDN)") (class "Default")
      (node (ref "J3") (pin "1") (pinfunction "1_1") (pintype "passive"))
      (node (ref "U2") (pin "7") (pinfunction "AUDN_7") (pintype "passive"))
    )
    (net (code "54") (name "Net-(U2-AUDP)") (class "Default")
      (node (ref "J3") (pin "2") (pinfunction "2_2") (pintype "passive"))
      (node (ref "U2") (pin "6") (pinfunction "AUDP_6") (pintype "passive"))
    )
    (net (code "55") (name "Net-(U3-PROG)") (class "Default")
      (node (ref "R10") (pin "2") (pinfunction "2_2") (pintype "passive"))
      (node (ref "U3") (pin "2") (pinfunction "PROG_2") (pintype "passive"))
    )
    (net (code "56") (name "Net-(U6-X1)") (class "Default")
      (node (ref "C19") (pin "2") (pinfunction "2_2") (pintype "passive"))
      (node (ref "U6") (pin "2") (pinfunction "X1_2") (pintype "passive"))
      (node (ref "X1") (pin "1") (pinfunction "OSC1_1") (pintype "passive"))
    )
    (net (code "57") (name "Net-(U6-X2)") (class "Default")
      (node (ref "C25") (pin "2") (pinfunction "2_2") (pintype "passive"))
      (node (ref "U6") (pin "3") (pinfunction "X2_3") (pintype "passive"))
      (node (ref "X1") (pin "2") (pinfunction "OSC2_2") (pintype "passive"))
    )
    (net (code "58") (name "Net-(U8-VDD)") (class "Default")
      (node (ref "C29") (pin "1") (pinfunction "1_1") (pintype "passive"))
      (node (ref "R23") (pin "2") (pinfunction "2_2") (pintype "passive"))
      (node (ref "U8") (pin "5") (pinfunction "VDD_5") (pintype "passive"))
    )
    (net (code "59") (name "Net-(USB1-VBUS)") (class "Default")
      (node (ref "F1") (pin "1") (pinfunction "1_1") (pintype "passive"))
      (node (ref "USB1") (pin "1") (pinfunction "VBUS_1") (pintype "passive"))
    )
    (net (code "60") (name "VCC_3V3") (class "Default")
      (node (ref "C10") (pin "2") (pinfunction "2_2") (pintype "passive"))
      (node (ref "C13") (pin "1") (pinfunction "1_1") (pintype "passive"))
      (node (ref "C14") (pin "1") (pinfunction "1_1") (pintype "passive"))
      (node (ref "C17") (pin "2") (pinfunction "2_2") (pintype "passive"))
      (node (ref "C18") (pin "2") (pinfunction "2_2") (pintype "passive"))
      (node (ref "C22") (pin "1") (pinfunction "1_1") (pintype "passive"))
      (node (ref "C23") (pin "1") (pinfunction "1_1") (pintype "passive"))
      (node (ref "C24") (pin "1") (pinfunction "1_1") (pintype "passive"))
      (node (ref "C26") (pin "1") (pinfunction "1_1") (pintype "passive"))
      (node (ref "C4") (pin "1") (pinfunction "1_1") (pintype "passive"))
      (node (ref "C6") (pin "2") (pinfunction "2_2") (pintype "passive"))
      (node (ref "C7") (pin "2") (pinfunction "2_2") (pintype "passive"))
      (node (ref "C8") (pin "2") (pinfunction "2_2") (pintype "passive"))
      (node (ref "C9") (pin "2") (pinfunction "2_2") (pintype "passive"))
      (node (ref "J1") (pin "1") (pinfunction "1_1") (pintype "passive"))
      (node (ref "L1") (pin "1") (pinfunction "1_1") (pintype "passive"))
      (node (ref "P1") (pin "13") (pinfunction "13_13") (pintype "passive"))
      (node (ref "P1") (pin "14") (pinfunction "14_14") (pintype "passive"))
      (node (ref "P2") (pin "1") (pinfunction "1_1") (pintype "passive"))
      (node (ref "P2") (pin "3") (pinfunction "3_3") (pintype "passive"))
      (node (ref "P2") (pin "5") (pinfunction "5_5") (pintype "passive"))
      (node (ref "R15") (pin "2") (pinfunction "2_2") (pintype "passive"))
      (node (ref "R16") (pin "2") (pinfunction "2_2") (pintype "passive"))
      (node (ref "R17") (pin "1") (pinfunction "1_1") (pintype "passive"))
      (node (ref "R18") (pin "2") (pinfunction "2_2") (pintype "passive"))
      (node (ref "R19") (pin "2") (pinfunction "2_2") (pintype "passive"))
      (node (ref "R21") (pin "2") (pinfunction "2_2") (pintype "passive"))
      (node (ref "R6") (pin "2") (pinfunction "2_2") (pintype "passive"))
      (node (ref "R8") (pin "2") (pinfunction "2_2") (pintype "passive"))
      (node (ref "R9") (pin "2") (pinfunction "2_2") (pintype "passive"))
      (node (ref "U1") (pin "5") (pinfunction "VDD_5") (pintype "passive"))
      (node (ref "U2") (pin "5") (pinfunction "PVDD_5") (pintype "passive"))
      (node (ref "U4") (pin "1") (pinfunction "VBAT_1") (pintype "passive"))
      (node (ref "U4") (pin "24") (pinfunction "VDD_1_24") (pintype "passive"))
      (node (ref "U4") (pin "36") (pinfunction "VDD_2_36") (pintype "passive"))
      (node (ref "U4") (pin "48") (pinfunction "VDD_3_48") (pintype "passive"))
      (node (ref "U5") (pin "2") (pinfunction "VOUT_2") (pintype "passive"))
      (node (ref "U5") (pin "4") (pinfunction "VOUT_4") (pintype "passive"))
      (node (ref "U6") (pin "1") (pinfunction "VCC2_1") (pintype "passive"))
      (node (ref "U6") (pin "8") (pinfunction "VCC1_8") (pintype "passive"))
      (node (ref "U7") (pin "1") (pinfunction "VDD_1") (pintype "passive"))
    )
    (net (code "61") (name "VCC_5V") (class "Default")
      (node (ref "C20") (pin "1") (pinfunction "1_1") (pintype "passive"))
      (node (ref "C21") (pin "1") (pinfunction "1_1") (pintype "passive"))
      (node (ref "D1") (pin "1") (pinfunction "K_1") (pintype "passive"))
      (node (ref "P3") (pin "1") (pinfunction "1_1") (pintype "passive"))
      (node (ref "P3") (pin "3") (pinfunction "3_3") (pintype "passive"))
      (node (ref "P3") (pin "5") (pinfunction "5_5") (pintype "passive"))
      (node (ref "Q3") (pin "3") (pinfunction "D_3") (pintype "passive"))
      (node (ref "U5") (pin "3") (pinfunction "VIN_3") (pintype "passive"))
    )
    (net (code "62") (name "VDDA") (class "Default")
      (node (ref "C15") (pin "2") (pinfunction "2_2") (pintype "passive"))
      (node (ref "C16") (pin "2") (pinfunction "2_2") (pintype "passive"))
      (node (ref "L1") (pin "2") (pinfunction "2_2") (pintype "passive"))
      (node (ref "U4") (pin "9") (pinfunction "VDDA_9") (pintype "passive"))
    )
    (net (code "63") (name "VIN_5V") (class "Default")
      (node (ref "C12") (pin "2") (pinfunction "2_2") (pintype "passive"))
      (node (ref "D1") (pin "2") (pinfunction "A_2") (pintype "passive"))
      (node (ref "F1") (pin "2") (pinfunction "2_2") (pintype "passive"))
      (node (ref "R11") (pin "2") (pinfunction "2_2") (pintype "passive"))
      (node (ref "R12") (pin "2") (pinfunction "2_2") (pintype "passive"))
      (node (ref "U3") (pin "4") (pinfunction "VCC_4") (pintype "passive"))
    )
    (net (code "64") (name "unconnected-(SW1-Pad1)") (class "Default")
      (node (ref "SW1") (pin "1") (pinfunction "1_1") (pintype "passive+no_connect"))
    )
    (net (code "65") (name "unconnected-(SW1-Pad3)") (class "Default")
      (node (ref "SW1") (pin "3") (pinfunction "3_3") (pintype "passive+no_connect"))
    )
    (net (code "66") (name "unconnected-(SW2-Pad1)") (class "Default")
      (node (ref "SW2") (pin "1") (pinfunction "1_1") (pintype "passive+no_connect"))
    )
    (net (code "67") (name "unconnected-(SW2-Pad3)") (class "Default")
      (node (ref "SW2") (pin "3") (pinfunction "3_3") (pintype "passive+no_connect"))
    )
    (net (code "68") (name "unconnected-(SW3-Pad1)") (class "Default")
      (node (ref "SW3") (pin "1") (pinfunction "1_1") (pintype "passive+no_connect"))
    )
    (net (code "69") (name "unconnected-(SW3-Pad3)") (class "Default")
      (node (ref "SW3") (pin "3") (pinfunction "3_3") (pintype "passive+no_connect"))
    )
    (net (code "70") (name "unconnected-(SW4-Pad1)") (class "Default")
      (node (ref "SW4") (pin "1") (pinfunction "1_1") (pintype "passive+no_connect"))
    )
    (net (code "71") (name "unconnected-(SW4-Pad3)") (class "Default")
      (node (ref "SW4") (pin "3") (pinfunction "3_3") (pintype "passive+no_connect"))
    )
    (net (code "72") (name "unconnected-(SW5-Pad1)") (class "Default")
      (node (ref "SW5") (pin "1") (pinfunction "1_1") (pintype "passive+no_connect"))
    )
    (net (code "73") (name "unconnected-(SW5-Pad3)") (class "Default")
      (node (ref "SW5") (pin "3") (pinfunction "3_3") (pintype "passive+no_connect"))
    )
    (net (code "74") (name "unconnected-(SW6-Pad1)") (class "Default")
      (node (ref "SW6") (pin "1") (pinfunction "1_1") (pintype "passive+no_connect"))
    )
    (net (code "75") (name "unconnected-(SW6-Pad3)") (class "Default")
      (node (ref "SW6") (pin "3") (pinfunction "3_3") (pintype "passive+no_connect"))
    )
    (net (code "76") (name "unconnected-(SW7-Pad3)") (class "Default")
      (node (ref "SW7") (pin "3") (pinfunction "3_3") (pintype "passive+no_connect"))
    )
    (net (code "77") (name "unconnected-(SW8-Pad1)") (class "Default")
      (node (ref "SW8") (pin "1") (pinfunction "1_1") (pintype "passive+no_connect"))
    )
    (net (code "78") (name "unconnected-(U2-VPP{slash}IOH3-Pad1)") (class "Default")
      (node (ref "U2") (pin "1") (pinfunction "VPP/IOH3_1") (pintype "passive+no_connect"))
    )
    (net (code "79") (name "unconnected-(U3-NC-Pad1)") (class "Default")
      (node (ref "U3") (pin "1") (pinfunction "NC_1") (pintype "passive+no_connect"))
    )
    (net (code "80") (name "unconnected-(U3-NC-Pad8)") (class "Default")
      (node (ref "U3") (pin "8") (pinfunction "NC_8") (pintype "passive+no_connect"))
    )
    (net (code "81") (name "unconnected-(U4-PC13-TAMPER-RTC-Pad2)") (class "Default")
      (node (ref "U4") (pin "2") (pinfunction "PC13-TAMPER-RTC_2") (pintype "passive"))
    )
    (net (code "82") (name "unconnected-(U4-PC14-OSC32_IN-Pad3)") (class "Default")
      (node (ref "U4") (pin "3") (pinfunction "PC14-OSC32_IN_3") (pintype "passive"))
    )
    (net (code "83") (name "unconnected-(U4-PC15-OSC32_OUT-Pad4)") (class "Default")
      (node (ref "U4") (pin "4") (pinfunction "PC15-OSC32_OUT_4") (pintype "passive"))
    )
    (net (code "84") (name "unconnected-(U7-NC-Pad3)") (class "Default")
      (node (ref "U7") (pin "3") (pinfunction "NC_3") (pintype "passive+no_connect"))
    )
    (net (code "85") (name "unconnected-(U8-NC-Pad4)") (class "Default")
      (node (ref "U8") (pin "4") (pinfunction "NC_4") (pintype "passive+no_connect"))
    )
    (net (code "86") (name "unconnected-(USB1-D+-Pad3)") (class "Default")
      (node (ref "USB1") (pin "3") (pinfunction "D+_3") (pintype "passive+no_connect"))
    )
    (net (code "87") (name "unconnected-(USB1-D--Pad2)") (class "Default")
      (node (ref "USB1") (pin "2") (pinfunction "D-_2") (pintype "passive+no_connect"))
    )
    (net (code "88") (name "unconnected-(USB1-ID-Pad4)") (class "Default")
      (node (ref "USB1") (pin "4") (pinfunction "ID_4") (pintype "passive+no_connect"))
    )
  )
)
